# Temperature_monitoring.net
KiCad netlist of a schematic drawn in Altium Designer
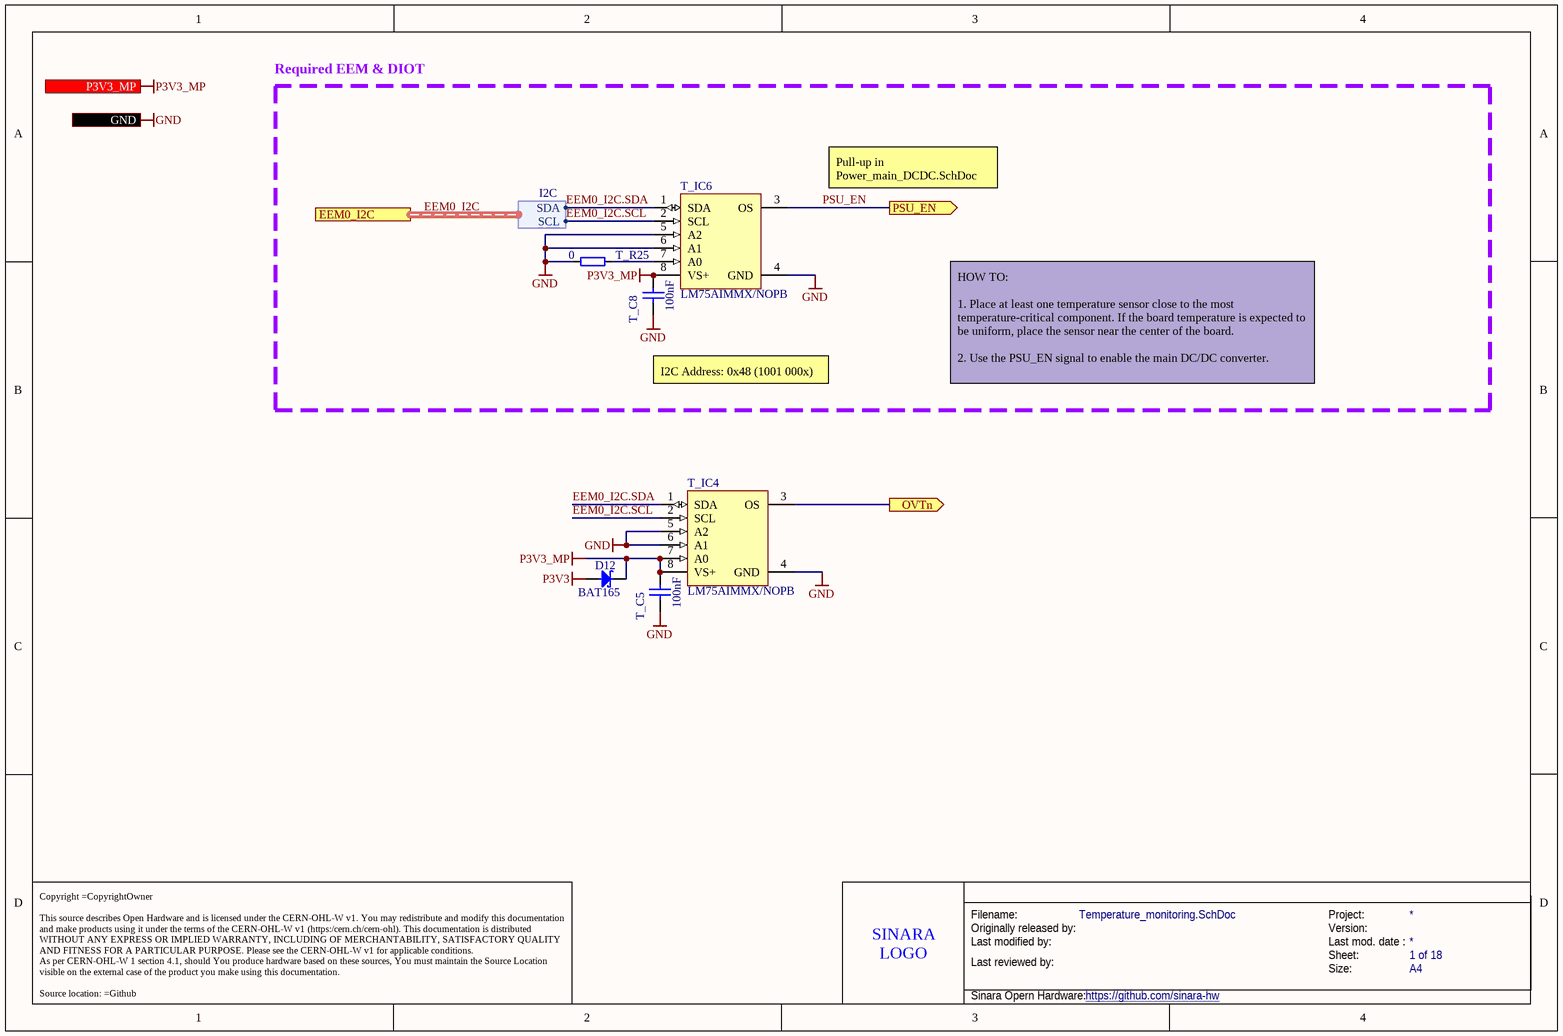
[diagram p0: Temperature_monitoring.SchDoc]

(export (version "E")
  (design (tool "Eeschema 10.0.6"))
  (components
    (comp (ref "D12")
      (value "BAT165")
      (footprint "SOD2512X110N")
      (description "Schottky Diode")
      (fields
        (field (name "VOLTAGE") "40V")
        (field (name "POWER") "750mA")
        (field (name "AUTHOR") "CERN DEM JLC")
      )
      (libsource (lib "ICs And Semiconductors") (part "Diode Schottky"))
    )
    (comp (ref "T_C5")
      (value "100nF")
      (footprint "CAPC1005X55N")
      (description "Non-polarised capacitor")
      (fields
        (field (name "PART NUMBER") "CC0402_100NF_50V_10%_X7R")
        (field (name "VOLTAGE") "50V")
        (field (name "AUTHOR") "CERN DEM MR")
      )
      (libsource (lib "Capacitors") (part "Capacitor - non polarized"))
    )
    (comp (ref "T_C8")
      (value "100nF")
      (footprint "CAPC1005X55N")
      (description "Non-polarised capacitor")
      (fields
        (field (name "PART NUMBER") "CC0402_100NF_50V_10%_X7R")
        (field (name "VOLTAGE") "50V")
        (field (name "AUTHOR") "CERN DEM MR")
      )
      (libsource (lib "Capacitors") (part "Capacitor - non polarized"))
    )
    (comp (ref "T_IC4")
      (value "LM75AIMMX/NOPB")
      (footprint "DGK0008A_M")
      (description "Serial Switch/Digital Sensor, 9 Bit(s), 3Cel, Square, 8 Pin, Surface Mount")
      (libsource (lib "TechnoSystem Workspace") (part "SEN-TEMP-LM75-8"))
    )
    (comp (ref "T_IC6")
      (value "LM75AIMMX/NOPB")
      (footprint "DGK0008A_M")
      (description "Serial Switch/Digital Sensor, 9 Bit(s), 3Cel, Square, 8 Pin, Surface Mount")
      (libsource (lib "TechnoSystem Workspace") (part "SEN-TEMP-LM75-8"))
    )
    (comp (ref "T_R25")
      (value "0")
      (footprint "RESC1005X40N")
      (description "Resistor")
      (fields
        (field (name "PART NUMBER") "R0402_0R_JUMPER")
        (field (name "MANUFACTURER") "GENERIC")
        (field (name "AUTHOR") "CERN DEM JLC")
      )
      (libsource (lib "Resistors") (part "Resistor"))
    )
  )
  (nets
    (net (code "2") (name "/EEM0_I2C.SCL") (class "Default")
      (node (ref "T_IC4") (pin "2") (pinfunction "SCL_2") (pintype "input"))
      (node (ref "T_IC6") (pin "2") (pinfunction "SCL_2") (pintype "input"))
    )
    (net (code "3") (name "/EEM0_I2C.SDA") (class "Default")
      (node (ref "T_IC4") (pin "1") (pinfunction "SDA_1") (pintype "bidirectional"))
      (node (ref "T_IC6") (pin "1") (pinfunction "SDA_1") (pintype "bidirectional"))
    )
    (net (code "5") (name "/OVTn") (class "Default")
      (node (ref "T_IC4") (pin "3") (pinfunction "OS_3") (pintype "open_collector"))
    )
    (net (code "6") (name "/PSU_EN") (class "Default")
      (node (ref "T_IC6") (pin "3") (pinfunction "OS_3") (pintype "open_collector"))
    )
    (net (code "7") (name "GND") (class "Default")
      (node (ref "T_C5") (pin "1") (pinfunction "1_1") (pintype "passive"))
      (node (ref "T_C8") (pin "1") (pinfunction "1_1") (pintype "passive"))
      (node (ref "T_IC4") (pin "4") (pinfunction "GND_4") (pintype "power_in"))
      (node (ref "T_IC4") (pin "5") (pinfunction "A2_5") (pintype "input"))
      (node (ref "T_IC4") (pin "6") (pinfunction "A1_6") (pintype "input"))
      (node (ref "T_IC6") (pin "4") (pinfunction "GND_4") (pintype "power_in"))
      (node (ref "T_IC6") (pin "5") (pinfunction "A2_5") (pintype "input"))
      (node (ref "T_IC6") (pin "6") (pinfunction "A1_6") (pintype "input"))
      (node (ref "T_R25") (pin "1") (pinfunction "1_1") (pintype "passive"))
    )
    (net (code "8") (name "Net-(T_IC6-A0)") (class "Default")
      (node (ref "T_IC6") (pin "7") (pinfunction "A0_7") (pintype "input"))
      (node (ref "T_R25") (pin "2") (pinfunction "2_2") (pintype "passive"))
    )
    (net (code "9") (name "P3V3") (class "Default")
      (node (ref "D12") (pin "2") (pinfunction "A_2") (pintype "passive"))
    )
    (net (code "10") (name "P3V3_MP") (class "Default")
      (node (ref "D12") (pin "1") (pinfunction "C_1") (pintype "passive"))
      (node (ref "T_C5") (pin "2") (pinfunction "2_2") (pintype "passive"))
      (node (ref "T_C8") (pin "2") (pinfunction "2_2") (pintype "passive"))
      (node (ref "T_IC4") (pin "7") (pinfunction "A0_7") (pintype "input"))
      (node (ref "T_IC4") (pin "8") (pinfunction "VS+_8") (pintype "power_in"))
      (node (ref "T_IC6") (pin "8") (pinfunction "VS+_8") (pintype "power_in"))
    )
  )
)
